# PLD_HK.net
KiCad netlist of a schematic drawn in Altium Designer
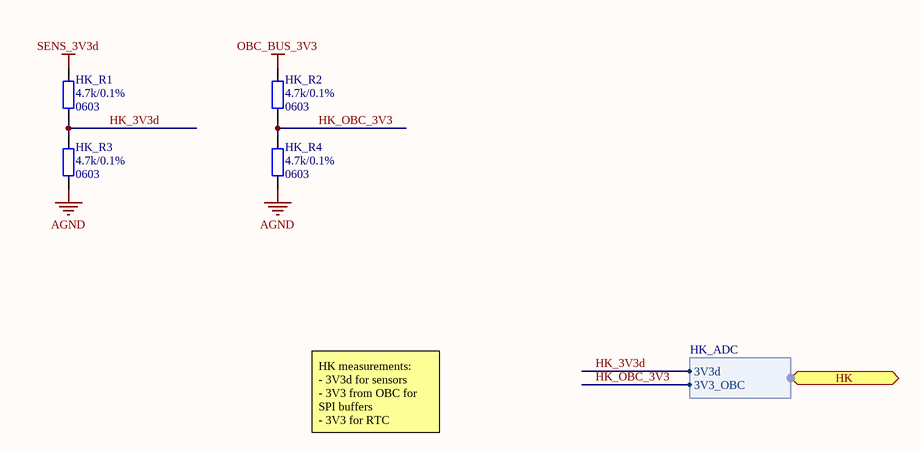
[diagram p0: PLD_HK.SchDoc]

(export (version "E")
  (design (tool "Eeschema 10.0.6"))
  (components
    (comp (ref "HK_R1")
      (value "4.7k/0.1%")
      (footprint "SMD_Resistor_0603")
      (fields (field (name "PACKAGE") "0603"))
      (libsource (lib "resistors") (part "Res"))
    )
    (comp (ref "HK_R2")
      (value "4.7k/0.1%")
      (footprint "SMD_Resistor_0603")
      (fields (field (name "PACKAGE") "0603"))
      (libsource (lib "resistors") (part "Res"))
    )
    (comp (ref "HK_R3")
      (value "4.7k/0.1%")
      (footprint "SMD_Resistor_0603")
      (fields (field (name "PACKAGE") "0603"))
      (libsource (lib "resistors") (part "Res"))
    )
    (comp (ref "HK_R4")
      (value "4.7k/0.1%")
      (footprint "SMD_Resistor_0603")
      (fields (field (name "PACKAGE") "0603"))
      (libsource (lib "resistors") (part "Res"))
    )
  )
  (nets
    (net (code "2") (name "/HK_3V3d") (class "Default")
      (node (ref "HK_R1") (pin "2") (pinfunction "2_2") (pintype "passive"))
      (node (ref "HK_R3") (pin "1") (pinfunction "1_1") (pintype "passive"))
    )
    (net (code "3") (name "/HK_OBC_3V3") (class "Default")
      (node (ref "HK_R2") (pin "2") (pinfunction "2_2") (pintype "passive"))
      (node (ref "HK_R4") (pin "1") (pinfunction "1_1") (pintype "passive"))
    )
    (net (code "5") (name "AGND") (class "Default")
      (node (ref "HK_R3") (pin "2") (pinfunction "2_2") (pintype "passive"))
      (node (ref "HK_R4") (pin "2") (pinfunction "2_2") (pintype "passive"))
    )
    (net (code "6") (name "OBC_BUS_3V3") (class "Default")
      (node (ref "HK_R2") (pin "1") (pinfunction "1_1") (pintype "passive"))
    )
    (net (code "7") (name "SENS_3V3d") (class "Default")
      (node (ref "HK_R1") (pin "1") (pinfunction "1_1") (pintype "passive"))
    )
  )
)
